# GSM_SDown_Control.net
KiCad netlist of a schematic drawn in Altium Designer
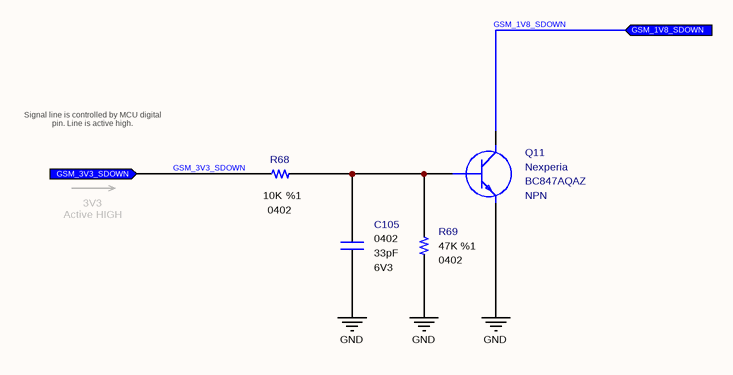
[diagram p0: GSM SDown Control.SchDoc]

(export (version "E")
  (design (tool "Eeschema 10.0.6"))
  (components
    (comp (ref "C105")
      (value "33pF")
      (footprint "CAPACITOR_0402")
      (description "Capacitor - 33pF [0402] (Ceramic)")
      (fields
        (field (name "CASE") "0402")
        (field (name "TOLERANCE") "10%")
        (field (name "VOLTAGE") "6V3")
        (field (name "MANUFACTURER PART NUMBER") "C0402C330J9RACAUTO")
      )
      (libsource (lib "Ovoo_Library") (part "Capacitor - 33pF [0402-6V3]"))
    )
    (comp (ref "Q11")
      (value "BC847AQAZ")
      (footprint "SOT1215")
      (description "Bipolar NPN Transistors")
      (fields
        (field (name "POLARITY") "NPN")
        (field (name "MANUFACTURER NAME") "Nexperia")
        (field (name "MANUFACTURER PART NUMBER") "BC847AQAZ")
      )
      (libsource (lib "Ovoo_Library") (part "Transistor - BC847"))
    )
    (comp (ref "R68")
      (value "10K")
      (footprint "RESISTOR_0402")
      (description "Thick Film Resistors - SMD 1/16 W 10 Kohms 1%")
      (fields
        (field (name "TOLERANCE") "%1")
        (field (name "CASE") "0402")
        (field (name "MANUFACTURER PART NUMBER") "CRCW040210K0FKED")
        (field (name "MOUSER PART NUMBER") "71-CRCW0402-10K-E3")
      )
      (libsource (lib "Ovoo_Library") (part "Resistor - 10K"))
    )
    (comp (ref "R69")
      (value "47K")
      (footprint "RESISTOR_0402")
      (description "Thick Film Resistors - SMD 1/16 W 47 Kohms 1%")
      (fields
        (field (name "TOLERANCE") "%1")
        (field (name "CASE") "0402")
        (field (name "MANUFACTURER PART NUMBER") "CRCW040247K0FKED")
        (field (name "Comment") "47K - 0402 - %1 - 1/16W")
      )
      (libsource (lib "Ovoo_Library") (part "Resistor - 47K"))
    )
  )
  (nets
    (net (code "1") (name "/GSM_1V8_SDOWN") (class "Default")
      (node (ref "Q11") (pin "3") (pinfunction "C_3") (pintype "passive"))
    )
    (net (code "2") (name "/GSM_3V3_SDOWN") (class "Default")
      (node (ref "R68") (pin "2") (pinfunction "2_2") (pintype "passive"))
    )
    (net (code "3") (name "GND") (class "Default")
      (node (ref "C105") (pin "2") (pinfunction "2_2") (pintype "passive"))
      (node (ref "Q11") (pin "2") (pinfunction "E_2") (pintype "passive"))
      (node (ref "R69") (pin "1") (pinfunction "1_1") (pintype "passive"))
    )
    (net (code "4") (name "Net-(Q11-B)") (class "Default")
      (node (ref "C105") (pin "1") (pinfunction "1_1") (pintype "passive"))
      (node (ref "Q11") (pin "1") (pinfunction "B_1") (pintype "passive"))
      (node (ref "R68") (pin "1") (pinfunction "1_1") (pintype "passive"))
      (node (ref "R69") (pin "2") (pinfunction "2_2") (pintype "passive"))
    )
  )
)
